# PWMSoldeerbout.net
KiCad netlist of a schematic drawn in Altium Designer
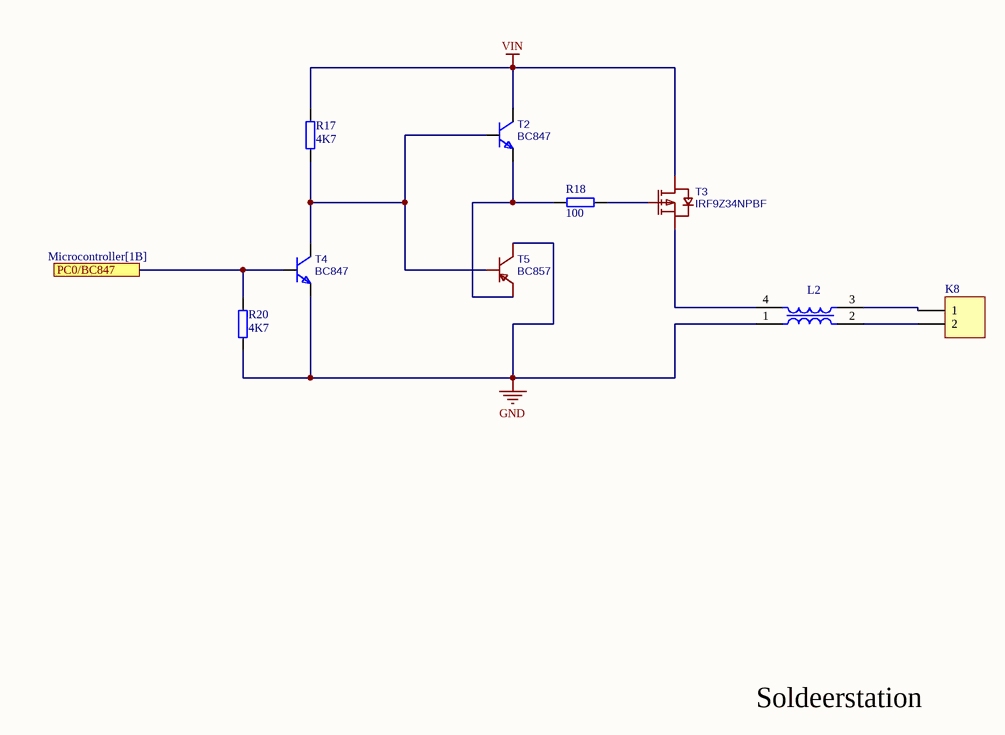
[diagram p0: PWMSoldeerbout.SchDoc]

(export (version "E")
  (design (tool "Eeschema 10.0.6"))
  (components
    (comp (ref "K8")
      (value "~")
      (footprint "HDR1X2")
      (description "Header, 2-Pin")
      (fields (field (name "PUBLISHER") "Altium Limited"))
      (libsource (lib "Miscellaneous Connectors") (part "Header 2"))
    )
    (comp (ref "L2")
      (value "~")
      (footprint "L1 Smoorspoel")
      (description "Common Mode Chokes / Filters 170ohms 100MHz 10A 1 Choke SMD")
      (fields
        (field (name "MOUSER PART NUMBER") "875-CM2545X171R-10")
        (field (name "MANUFACTURER_PART_NUMBER") "CM2545X171R-10")
      )
      (libsource (lib "SoldeerStation") (part "L2 Common Mode Choke"))
    )
    (comp (ref "R17")
      (value "4K7")
      (footprint "RESC2013X50X30ML20T20")
      (fields (field (name "MANUFACTURER") "Vishay Dale") (field (name "PART NUMBER") "CRCW08050000Z0EA"))
      (libsource (lib "SoldeerStation") (part "R Resistor"))
    )
    (comp (ref "R18")
      (value "100")
      (footprint "RESC2013X50X30ML20T20")
      (fields (field (name "MANUFACTURER") "Vishay Dale") (field (name "PART NUMBER") "CRCW08050000Z0EA"))
      (libsource (lib "SoldeerStation") (part "R Resistor"))
    )
    (comp (ref "R20")
      (value "4K7")
      (footprint "RESC2013X50X30ML20T20")
      (fields (field (name "MANUFACTURER") "Vishay Dale") (field (name "PART NUMBER") "CRCW08050000Z0EA"))
      (libsource (lib "SoldeerStation") (part "R Resistor"))
    )
    (comp (ref "T2")
      (value "BC847")
      (footprint "T1,2,4 Bipolar Transistors")
      (description "BC847C_C3027113")
      (fields
        (field (name "BOM_SUPPLIER PART") "C3027113")
        (field (name "BOM_MANUFACTURER PART") "BC847C")
        (field (name "CONTRIBUTOR") "lcsc")
      )
      (libsource (lib "SoldeerStation") (part "T1,2,4 transisitors"))
    )
    (comp (ref "T3")
      (value "IRF9Z34NPBF")
      (footprint "T3 MOSFET-P")
      (fields (field (name "BOM_SUPPLIER PART") "C500523") (field (name "CONTRIBUTOR") "LCSC"))
      (libsource (lib "SoldeerStation") (part "T3 MOSFET-P"))
    )
    (comp (ref "T4")
      (value "BC847")
      (footprint "T1,2,4 Bipolar Transistors")
      (description "BC847C_C3027113")
      (fields
        (field (name "BOM_SUPPLIER PART") "C3027113")
        (field (name "BOM_MANUFACTURER PART") "BC847C")
        (field (name "CONTRIBUTOR") "lcsc")
      )
      (libsource (lib "SoldeerStation") (part "T1,2,4 transisitors"))
    )
    (comp (ref "T5")
      (value "BC857")
      (footprint "T5 Bipolar Transistors")
      (description "BC857 3G")
      (fields (field (name "BOM_SUPPLIER PART") "C2139"))
      (libsource (lib "SoldeerStation") (part "T5 Bipolar Transistor"))
    )
  )
  (nets
    (net (code "1") (name "/PC0{slash}BC847") (class "Default")
      (node (ref "R20") (pin "2") (pinfunction "2_2") (pintype "passive"))
      (node (ref "T4") (pin "1") (pinfunction "B_1") (pintype "passive"))
    )
    (net (code "2") (name "GND") (class "Default")
      (node (ref "L2") (pin "1") (pintype "passive"))
      (node (ref "R20") (pin "1") (pinfunction "1_1") (pintype "passive"))
      (node (ref "T4") (pin "2") (pinfunction "E_2") (pintype "passive"))
      (node (ref "T5") (pin "3") (pinfunction "3_3") (pintype "passive"))
    )
    (net (code "3") (name "Net-(K8-Pad1)") (class "Default")
      (node (ref "K8") (pin "1") (pinfunction "1_1") (pintype "passive"))
      (node (ref "L2") (pin "3") (pintype "passive"))
    )
    (net (code "4") (name "Net-(K8-Pad2)") (class "Default")
      (node (ref "K8") (pin "2") (pinfunction "2_2") (pintype "passive"))
      (node (ref "L2") (pin "2") (pintype "passive"))
    )
    (net (code "5") (name "Net-(T2-B)") (class "Default")
      (node (ref "R17") (pin "1") (pinfunction "1_1") (pintype "passive"))
      (node (ref "T2") (pin "1") (pinfunction "B_1") (pintype "passive"))
      (node (ref "T4") (pin "3") (pinfunction "C_3") (pintype "passive"))
      (node (ref "T5") (pin "1") (pinfunction "1_1") (pintype "passive"))
    )
    (net (code "6") (name "Net-(T2-E)") (class "Default")
      (node (ref "R18") (pin "2") (pinfunction "2_2") (pintype "passive"))
      (node (ref "T2") (pin "2") (pinfunction "E_2") (pintype "passive"))
      (node (ref "T5") (pin "2") (pinfunction "2_2") (pintype "passive"))
    )
    (net (code "7") (name "Net-(T3-G)") (class "Default")
      (node (ref "R18") (pin "1") (pinfunction "1_1") (pintype "passive"))
      (node (ref "T3") (pin "1") (pinfunction "G_1") (pintype "passive"))
    )
    (net (code "8") (name "Net-(T3-S)") (class "Default")
      (node (ref "L2") (pin "4") (pintype "passive"))
      (node (ref "T3") (pin "3") (pinfunction "S_3") (pintype "passive"))
    )
    (net (code "9") (name "VIN") (class "Default")
      (node (ref "R17") (pin "2") (pinfunction "2_2") (pintype "passive"))
      (node (ref "T2") (pin "3") (pinfunction "C_3") (pintype "passive"))
      (node (ref "T3") (pin "2") (pinfunction "D_2") (pintype "passive"))
    )
  )
)
